# 06_GPRS.net
KiCad netlist of a schematic drawn in Altium Designer
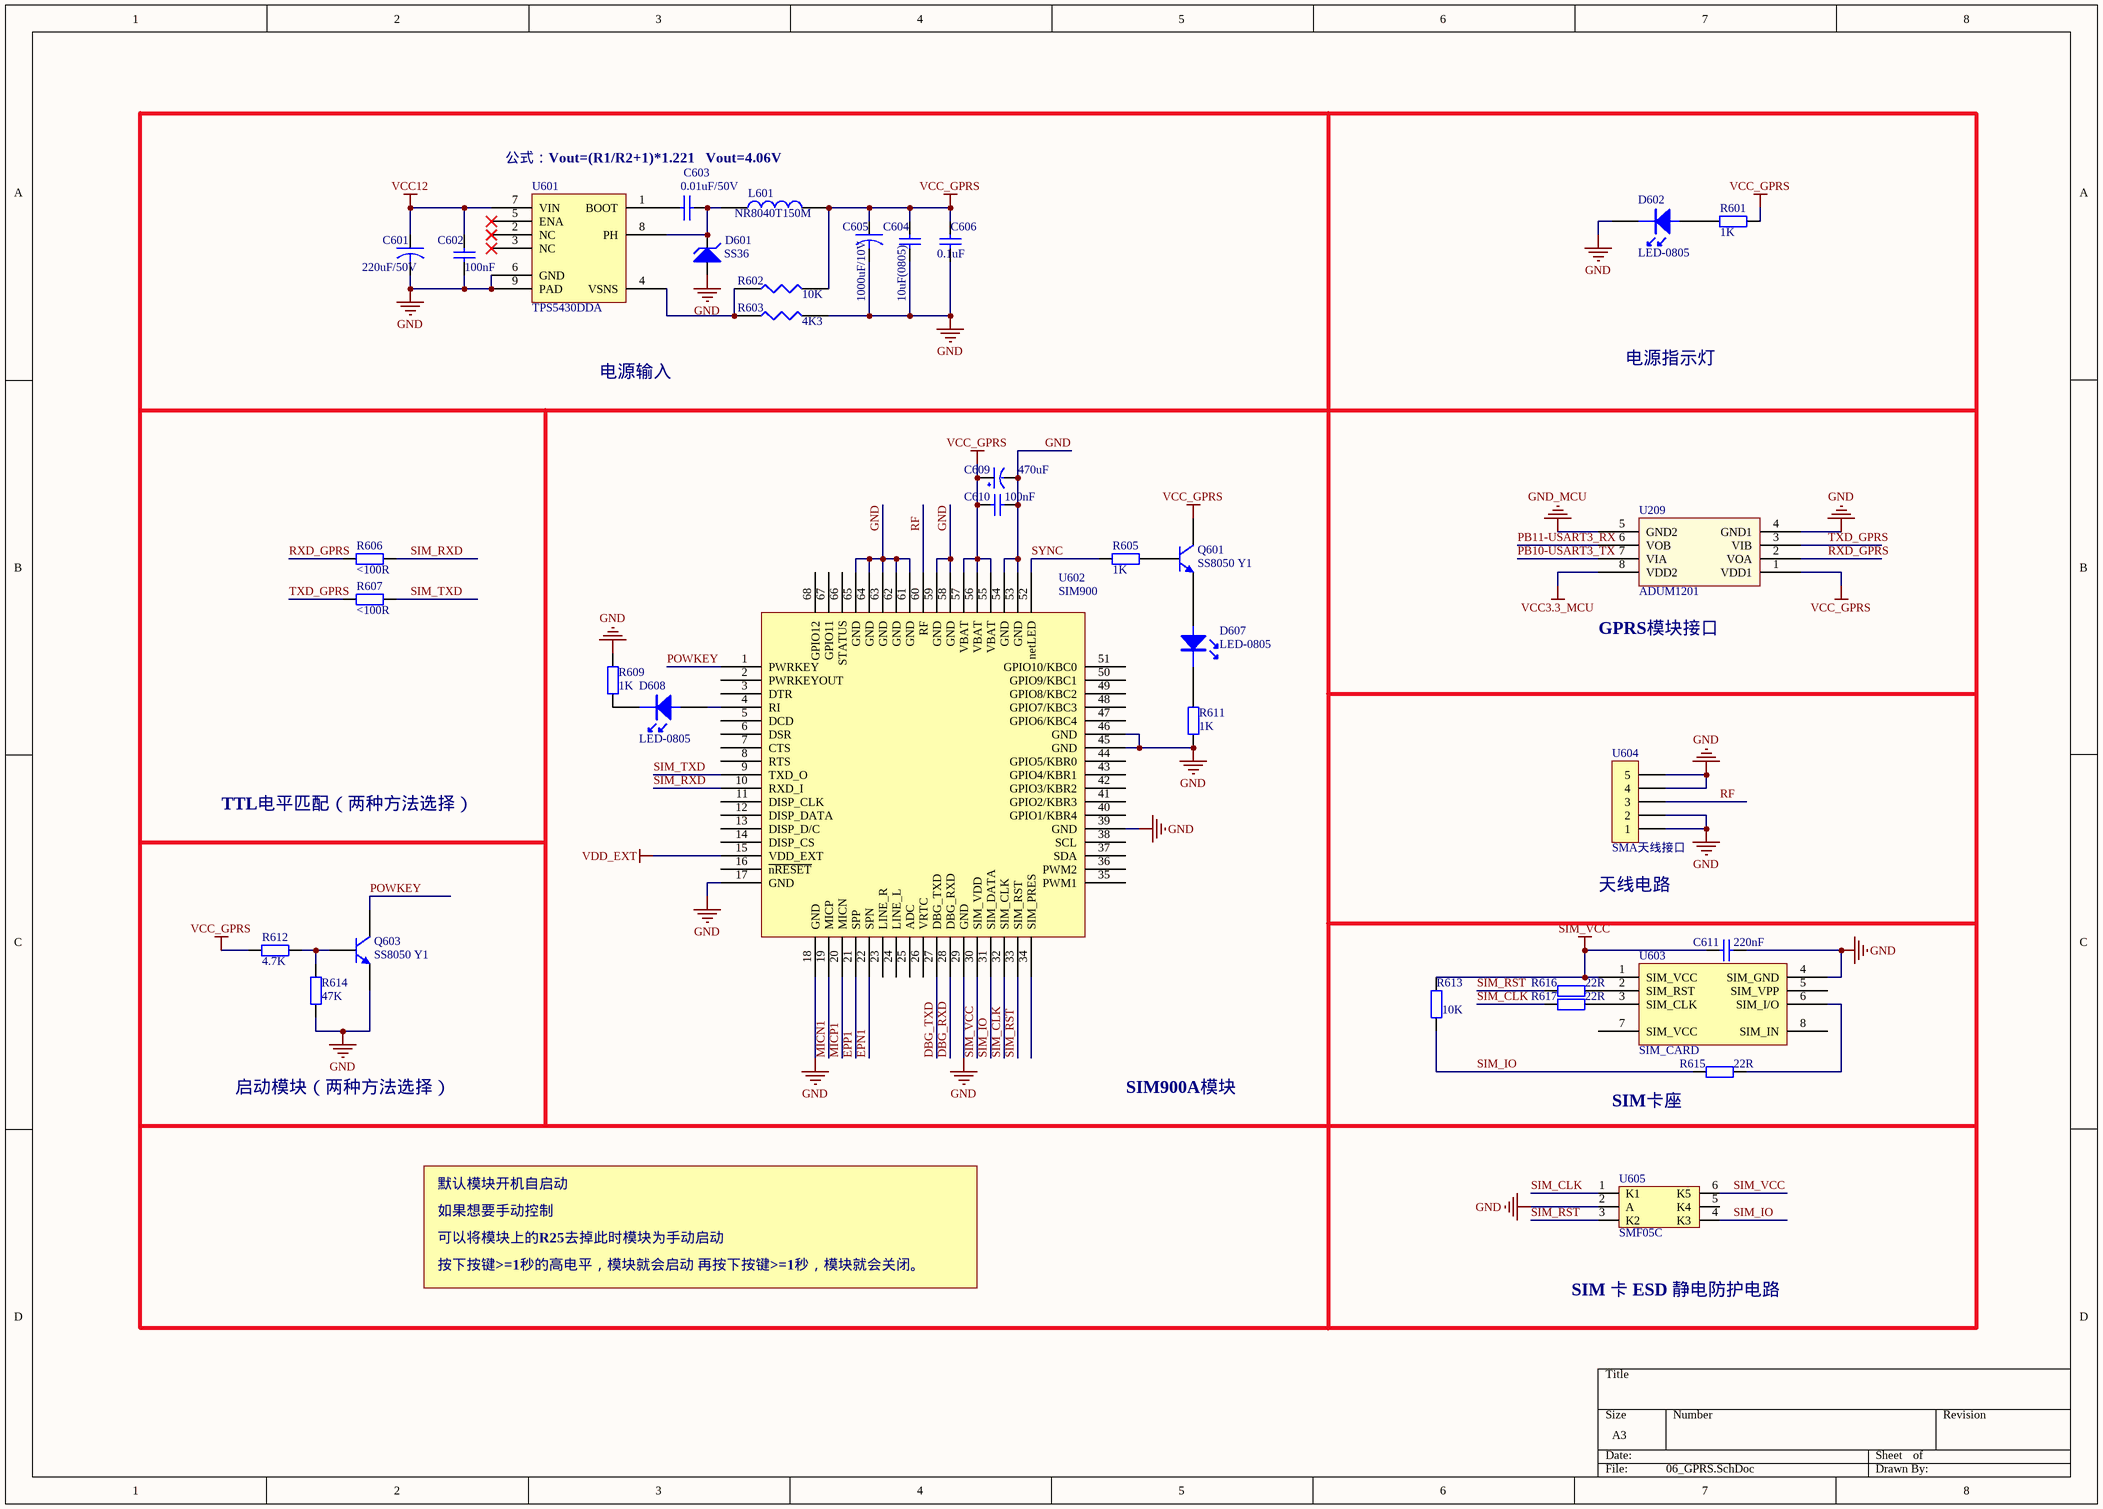
[diagram p0: 06_GPRS.SchDoc]

(export (version "E")
  (design (tool "Eeschema 10.0.6"))
  (components
    (comp (ref "C601")
      (value "220uF/50V")
      (footprint "CD's_LIB_2018:RB050-100")
      (description "Capacitor")
      (libsource (lib "*") (part "CAPACITOR"))
    )
    (comp (ref "C602")
      (value "100nF")
      (footprint "0805C")
      (description "贴片电容")
      (libsource (lib "Miscellaneous Devices LC") (part "0603 1uF (105) 10% 50V"))
    )
    (comp (ref "C603")
      (value "0.01uF/50V")
      (footprint "0603C")
      (description "Capacitor")
      (libsource (lib "*") (part "CAP"))
    )
    (comp (ref "C604")
      (value "10uF(0805)")
      (footprint "LC-0603_C")
      (description "贴片电容")
      (libsource (lib "Miscellaneous Devices LC") (part "0603 1uF (105) 10% 50V"))
    )
    (comp (ref "C605")
      (value "1000uF/10V")
      (footprint "RB035-080")
      (description "Capacitor")
      (libsource (lib "*") (part "CAPACITOR"))
    )
    (comp (ref "C606")
      (value "0.1uF")
      (footprint "LC-0603_C")
      (description "贴片电容")
      (libsource (lib "Miscellaneous Devices LC") (part "0603 1.0pF (010) 0.25pF 50V"))
    )
    (comp (ref "C609")
      (value "470uF")
      (footprint "CAP_10*10")
      (libsource (lib "Explorer STM32F407封装库") (part "CAP"))
    )
    (comp (ref "C610")
      (value "100nF")
      (footprint "LC-0603_C")
      (description "贴片电容")
      (libsource (lib "Miscellaneous Devices LC") (part "0603 1uF (105) 10% 50V"))
    )
    (comp (ref "C611")
      (value "220nF")
      (footprint "LC-0603_C")
      (description "贴片电容")
      (libsource (lib "Miscellaneous Devices LC") (part "0603 1uF (105) 10% 50V"))
    )
    (comp (ref "D601")
      (value "SS36")
      (footprint "D1812")
      (description "Zener Diode")
      (libsource (lib "*") (part "SS36"))
    )
    (comp (ref "D602")
      (value "LED-0805")
      (footprint "CD's_LIB_2018:0805LED")
      (description "贴片LED")
      (libsource (lib "CD's_LIB_2018") (part "LED_SMD"))
    )
    (comp (ref "D607")
      (value "LED-0805")
      (footprint "CD's_LIB_2018:0805LED")
      (description "贴片LED")
      (libsource (lib "CD's_LIB_2018") (part "LED_SMD"))
    )
    (comp (ref "D608")
      (value "LED-0805")
      (footprint "CD's_LIB_2018:0805LED")
      (description "贴片LED")
      (libsource (lib "CD's_LIB_2018") (part "LED_SMD"))
    )
    (comp (ref "L601") (value "NR8040T150M") (footprint "NR8040") (libsource (lib "*") (part "INDUCTOR")))
    (comp (ref "Q601")
      (value "SS8050 Y1")
      (footprint "LC-SOT-23(SOT-23-3)")
      (description "三极管")
      (libsource (lib "Miscellaneous Devices LC") (part "SOT-23 SS8050 Y1"))
    )
    (comp (ref "Q603")
      (value "SS8050 Y1")
      (footprint "LC-SOT-23(SOT-23-3)")
      (description "三极管")
      (libsource (lib "Miscellaneous Devices LC") (part "SOT-23 SS8050 Y1"))
    )
    (comp (ref "R601")
      (value "1K")
      (footprint "LC-0603_R")
      (description "贴片电阻")
      (libsource (lib "") (part "0603 2KΩ (2001) 1%_2"))
    )
    (comp (ref "R602") (value "10K") (footprint "0603R") (libsource (lib "*") (part "RES1")))
    (comp (ref "R603") (value "4K3") (footprint "0603R") (libsource (lib "*") (part "RES1")))
    (comp (ref "R605")
      (value "1K")
      (footprint "LC-0603_R")
      (description "贴片电阻")
      (libsource (lib "") (part "0603 2KΩ (2001) 1%_2"))
    )
    (comp (ref "R606")
      (value "<100R")
      (footprint "LC-0603_R")
      (description "贴片电阻")
      (libsource (lib "") (part "0603 2KΩ (2001) 1%_1"))
    )
    (comp (ref "R607")
      (value "<100R")
      (footprint "LC-0603_R")
      (description "贴片电阻")
      (libsource (lib "") (part "0603 2KΩ (2001) 1%_1"))
    )
    (comp (ref "R609")
      (value "1K")
      (footprint "LC-0603_R")
      (description "贴片电阻")
      (libsource (lib "") (part "0603 2KΩ (2001) 1%_3"))
    )
    (comp (ref "R611")
      (value "1K")
      (footprint "LC-0603_R")
      (description "贴片电阻")
      (libsource (lib "Miscellaneous Devices LC") (part "0603 2KΩ (2001) 1%"))
    )
    (comp (ref "R612")
      (value "4.7K")
      (footprint "LC-0603_R")
      (description "贴片电阻")
      (libsource (lib "") (part "0603 2KΩ (2001) 1%_1"))
    )
    (comp (ref "R613")
      (value "10K")
      (footprint "LC-0603_R")
      (description "贴片电阻")
      (libsource (lib "") (part "0603 2KΩ (2001) 1%_3"))
    )
    (comp (ref "R614")
      (value "47K")
      (footprint "LC-0603_R")
      (description "贴片电阻")
      (libsource (lib "") (part "0603 2KΩ (2001) 1%_3"))
    )
    (comp (ref "R615")
      (value "22R")
      (footprint "LC-0603_R")
      (description "贴片电阻")
      (libsource (lib "") (part "0603 2KΩ (2001) 1%_2"))
    )
    (comp (ref "R616")
      (value "22R")
      (footprint "LC-0603_R")
      (description "贴片电阻")
      (libsource (lib "") (part "0603 2KΩ (2001) 1%_2"))
    )
    (comp (ref "R617")
      (value "22R")
      (footprint "LC-0603_R")
      (description "贴片电阻")
      (libsource (lib "") (part "0603 2KΩ (2001) 1%_2"))
    )
    (comp (ref "U209")
      (value "ADUM1201")
      (footprint "SOP_8")
      (description "串口隔离")
      (libsource (lib "liu_2016") (part "ADUM1201"))
    )
    (comp (ref "U601") (value "TPS5430DDA") (footprint "SO-G8") (libsource (lib "*") (part "TPS5430DDA")))
    (comp (ref "U602")
      (value "SIM900")
      (footprint "SIM900A_mini:GSM_900A")
      (libsource (lib "ATK-SIM900A") (part "SIM900"))
    )
    (comp (ref "U603")
      (value "SIM_CARD")
      (footprint "MICRO SIM6")
      (description "SIM中卡卡槽")
      (libsource (lib "liu_2016") (part "SIM_CARD"))
    )
    (comp (ref "U604")
      (value "SMA天线接口")
      (footprint "RF_2")
      (description "Connector")
      (libsource (lib "CD's_LIB_2018") (part "CON5"))
    )
    (comp (ref "U605")
      (value "SMF05C")
      (footprint "SOT-363")
      (description "TVS")
      (libsource (lib "ATK-SIM900A GSM模块封装库") (part "SMF05C"))
    )
  )
  (nets
    (net (code "1") (name "/DBG_RXD") (class "Default")
      (node (ref "U602") (pin "28") (pinfunction "DBG_RXD_28") (pintype "passive"))
    )
    (net (code "2") (name "/DBG_TXD") (class "Default")
      (node (ref "U602") (pin "27") (pinfunction "DBG_TXD_27") (pintype "passive"))
    )
    (net (code "3") (name "/EPN1") (class "Default")
      (node (ref "U602") (pin "22") (pinfunction "SPN_22") (pintype "passive"))
    )
    (net (code "4") (name "/EPP1") (class "Default")
      (node (ref "U602") (pin "21") (pinfunction "SPP_21") (pintype "passive"))
    )
    (net (code "5") (name "/MICN1") (class "Default")
      (node (ref "U602") (pin "19") (pinfunction "MICP_19") (pintype "passive"))
    )
    (net (code "6") (name "/MICP1") (class "Default")
      (node (ref "U602") (pin "20") (pinfunction "MICN_20") (pintype "passive"))
    )
    (net (code "7") (name "/PB10-USART3_TX") (class "Default")
      (node (ref "U209") (pin "7") (pinfunction "VIA_7") (pintype "passive"))
    )
    (net (code "8") (name "/PB11-USART3_RX") (class "Default")
      (node (ref "U209") (pin "6") (pinfunction "VOB_6") (pintype "passive"))
    )
    (net (code "9") (name "/POWKEY") (class "Default")
      (node (ref "Q603") (pin "3") (pinfunction "C_3") (pintype "passive"))
      (node (ref "U602") (pin "1") (pinfunction "PWRKEY_1") (pintype "passive"))
    )
    (net (code "10") (name "/RF") (class "Default")
      (node (ref "U602") (pin "60") (pinfunction "RF_60") (pintype "passive"))
      (node (ref "U604") (pin "3") (pinfunction "3_3") (pintype "passive"))
    )
    (net (code "11") (name "/RXD_GPRS") (class "Default")
      (node (ref "R606") (pin "1") (pinfunction "1_1") (pintype "passive"))
      (node (ref "U209") (pin "2") (pinfunction "VOA_2") (pintype "passive"))
    )
    (net (code "12") (name "/SIM_CLK") (class "Default")
      (node (ref "R617") (pin "2") (pinfunction "2_2") (pintype "passive"))
      (node (ref "U602") (pin "32") (pinfunction "SIM_CLK_32") (pintype "passive"))
      (node (ref "U605") (pin "1") (pinfunction "K1_1") (pintype "passive"))
    )
    (net (code "13") (name "/SIM_IO") (class "Default")
      (node (ref "R613") (pin "1") (pinfunction "1_1") (pintype "passive"))
      (node (ref "R615") (pin "2") (pinfunction "2_2") (pintype "passive"))
      (node (ref "U602") (pin "31") (pinfunction "SIM_DATA_31") (pintype "passive"))
      (node (ref "U605") (pin "4") (pinfunction "K3_4") (pintype "passive"))
    )
    (net (code "14") (name "/SIM_RST") (class "Default")
      (node (ref "R616") (pin "2") (pinfunction "2_2") (pintype "passive"))
      (node (ref "U602") (pin "33") (pinfunction "SIM_RST_33") (pintype "passive"))
      (node (ref "U605") (pin "3") (pinfunction "K2_3") (pintype "passive"))
    )
    (net (code "15") (name "/SIM_RXD") (class "Default")
      (node (ref "R606") (pin "2") (pinfunction "2_2") (pintype "passive"))
      (node (ref "U602") (pin "10") (pinfunction "RXD_I_10") (pintype "passive"))
    )
    (net (code "16") (name "/SIM_TXD") (class "Default")
      (node (ref "R607") (pin "2") (pinfunction "2_2") (pintype "passive"))
      (node (ref "U602") (pin "9") (pinfunction "TXD_O_9") (pintype "passive"))
    )
    (net (code "17") (name "/SYNC") (class "Default")
      (node (ref "R605") (pin "2") (pinfunction "2_2") (pintype "passive"))
      (node (ref "U602") (pin "52") (pinfunction "netLED_52") (pintype "passive"))
    )
    (net (code "18") (name "/TXD_GPRS") (class "Default")
      (node (ref "R607") (pin "1") (pinfunction "1_1") (pintype "passive"))
      (node (ref "U209") (pin "3") (pinfunction "VIB_3") (pintype "passive"))
    )
    (net (code "19") (name "GND") (class "Default")
      (node (ref "C601") (pin "2") (pinfunction "2_2") (pintype "passive"))
      (node (ref "C602") (pin "2") (pinfunction "2_2") (pintype "passive"))
      (node (ref "C604") (pin "2") (pinfunction "2_2") (pintype "passive"))
      (node (ref "C605") (pin "2") (pinfunction "2_2") (pintype "passive"))
      (node (ref "C606") (pin "1") (pinfunction "1_1") (pintype "passive"))
      (node (ref "C609") (pin "2") (pinfunction "GND_2") (pintype "passive"))
      (node (ref "C610") (pin "2") (pinfunction "2_2") (pintype "passive"))
      (node (ref "C611") (pin "2") (pinfunction "2_2") (pintype "passive"))
      (node (ref "D601") (pin "1") (pinfunction "A_1") (pintype "passive"))
      (node (ref "D602") (pin "1") (pinfunction "-_1") (pintype "passive"))
      (node (ref "Q603") (pin "2") (pinfunction "E_2") (pintype "passive"))
      (node (ref "R603") (pin "2") (pinfunction "2_2") (pintype "passive"))
      (node (ref "R609") (pin "2") (pinfunction "2_2") (pintype "passive"))
      (node (ref "R611") (pin "2") (pinfunction "2_2") (pintype "passive"))
      (node (ref "R614") (pin "1") (pinfunction "1_1") (pintype "passive"))
      (node (ref "U209") (pin "4") (pinfunction "GND1_4") (pintype "passive"))
      (node (ref "U601") (pin "6") (pinfunction "GND_6") (pintype "passive"))
      (node (ref "U601") (pin "9") (pinfunction "PAD_9") (pintype "passive"))
      (node (ref "U602") (pin "17") (pinfunction "GND_17") (pintype "passive"))
      (node (ref "U602") (pin "18") (pinfunction "GND_18") (pintype "passive"))
      (node (ref "U602") (pin "29") (pinfunction "GND_29") (pintype "passive"))
      (node (ref "U602") (pin "39") (pinfunction "GND_39") (pintype "passive"))
      (node (ref "U602") (pin "45") (pinfunction "GND_45") (pintype "passive"))
      (node (ref "U602") (pin "46") (pinfunction "GND_46") (pintype "passive"))
      (node (ref "U602") (pin "53") (pinfunction "GND_53") (pintype "passive"))
      (node (ref "U602") (pin "54") (pinfunction "GND_54") (pintype "passive"))
      (node (ref "U602") (pin "58") (pinfunction "GND_58") (pintype "passive"))
      (node (ref "U602") (pin "59") (pinfunction "GND_59") (pintype "passive"))
      (node (ref "U602") (pin "61") (pinfunction "GND_61") (pintype "passive"))
      (node (ref "U602") (pin "62") (pinfunction "GND_62") (pintype "passive"))
      (node (ref "U602") (pin "63") (pinfunction "GND_63") (pintype "passive"))
      (node (ref "U602") (pin "64") (pinfunction "GND_64") (pintype "passive"))
      (node (ref "U602") (pin "65") (pinfunction "GND_65") (pintype "passive"))
      (node (ref "U603") (pin "4") (pinfunction "SIM_GND_4") (pintype "passive"))
      (node (ref "U604") (pin "1") (pinfunction "1_1") (pintype "passive"))
      (node (ref "U604") (pin "2") (pinfunction "2_2") (pintype "passive"))
      (node (ref "U604") (pin "4") (pinfunction "4_4") (pintype "passive"))
      (node (ref "U604") (pin "5") (pinfunction "5_5") (pintype "passive"))
      (node (ref "U605") (pin "2") (pinfunction "A_2") (pintype "passive"))
    )
    (net (code "20") (name "GND_MCU") (class "Default")
      (node (ref "U209") (pin "5") (pinfunction "GND2_5") (pintype "passive"))
    )
    (net (code "21") (name "Net-(D601-K)") (class "Default")
      (node (ref "C603") (pin "2") (pinfunction "2_2") (pintype "passive"))
      (node (ref "D601") (pin "2") (pinfunction "K_2") (pintype "passive"))
      (node (ref "L601") (pin "1") (pinfunction "1_1") (pintype "passive"))
      (node (ref "U601") (pin "8") (pinfunction "PH_8") (pintype "passive"))
    )
    (net (code "22") (name "Net-(D602-+)") (class "Default")
      (node (ref "D602") (pin "2") (pinfunction "+_2") (pintype "passive"))
      (node (ref "R601") (pin "2") (pinfunction "2_2") (pintype "passive"))
    )
    (net (code "23") (name "Net-(D607-+)") (class "Default")
      (node (ref "D607") (pin "2") (pinfunction "+_2") (pintype "passive"))
      (node (ref "Q601") (pin "2") (pinfunction "E_2") (pintype "passive"))
    )
    (net (code "24") (name "Net-(D607--)") (class "Default")
      (node (ref "D607") (pin "1") (pinfunction "-_1") (pintype "passive"))
      (node (ref "R611") (pin "1") (pinfunction "1_1") (pintype "passive"))
    )
    (net (code "25") (name "Net-(D608-+)") (class "Default")
      (node (ref "D608") (pin "2") (pinfunction "+_2") (pintype "passive"))
      (node (ref "U602") (pin "4") (pinfunction "RI_4") (pintype "passive"))
    )
    (net (code "26") (name "Net-(D608--)") (class "Default")
      (node (ref "D608") (pin "1") (pinfunction "-_1") (pintype "passive"))
      (node (ref "R609") (pin "1") (pinfunction "1_1") (pintype "passive"))
    )
    (net (code "27") (name "Net-(Q601-B)") (class "Default")
      (node (ref "Q601") (pin "1") (pinfunction "B_1") (pintype "passive"))
      (node (ref "R605") (pin "1") (pinfunction "1_1") (pintype "passive"))
    )
    (net (code "28") (name "Net-(Q603-B)") (class "Default")
      (node (ref "Q603") (pin "1") (pinfunction "B_1") (pintype "passive"))
      (node (ref "R612") (pin "2") (pinfunction "2_2") (pintype "passive"))
      (node (ref "R614") (pin "2") (pinfunction "2_2") (pintype "passive"))
    )
    (net (code "29") (name "Net-(U601-BOOT)") (class "Default")
      (node (ref "C603") (pin "1") (pinfunction "1_1") (pintype "passive"))
      (node (ref "U601") (pin "1") (pinfunction "BOOT_1") (pintype "passive"))
    )
    (net (code "30") (name "Net-(U601-VSNS)") (class "Default")
      (node (ref "R602") (pin "1") (pinfunction "1_1") (pintype "passive"))
      (node (ref "R603") (pin "1") (pinfunction "1_1") (pintype "passive"))
      (node (ref "U601") (pin "4") (pinfunction "VSNS_4") (pintype "passive"))
    )
    (net (code "31") (name "Net-(U603-SIM_CLK)") (class "Default")
      (node (ref "R617") (pin "1") (pinfunction "1_1") (pintype "passive"))
      (node (ref "U603") (pin "3") (pinfunction "SIM_CLK_3") (pintype "passive"))
    )
    (net (code "32") (name "Net-(U603-SIM_I{slash}O)") (class "Default")
      (node (ref "R615") (pin "1") (pinfunction "1_1") (pintype "passive"))
      (node (ref "U603") (pin "6") (pinfunction "SIM_I/O_6") (pintype "passive"))
    )
    (net (code "33") (name "Net-(U603-SIM_RST)") (class "Default")
      (node (ref "R616") (pin "1") (pinfunction "1_1") (pintype "passive"))
      (node (ref "U603") (pin "2") (pinfunction "SIM_RST_2") (pintype "passive"))
    )
    (net (code "34") (name "SIM_VCC") (class "Default")
      (node (ref "C611") (pin "1") (pinfunction "1_1") (pintype "passive"))
      (node (ref "R613") (pin "2") (pinfunction "2_2") (pintype "passive"))
      (node (ref "U602") (pin "30") (pinfunction "SIM_VDD_30") (pintype "passive"))
      (node (ref "U603") (pin "1") (pinfunction "SIM_VCC_1") (pintype "passive"))
      (node (ref "U605") (pin "6") (pinfunction "K5_6") (pintype "passive"))
    )
    (net (code "35") (name "VCC3.3_MCU") (class "Default")
      (node (ref "U209") (pin "8") (pinfunction "VDD2_8") (pintype "passive"))
    )
    (net (code "36") (name "VCC12") (class "Default")
      (node (ref "C601") (pin "1") (pinfunction "1_1") (pintype "passive"))
      (node (ref "C602") (pin "1") (pinfunction "1_1") (pintype "passive"))
      (node (ref "U601") (pin "7") (pinfunction "VIN_7") (pintype "passive"))
    )
    (net (code "37") (name "VCC_GPRS") (class "Default")
      (node (ref "C604") (pin "1") (pinfunction "1_1") (pintype "passive"))
      (node (ref "C605") (pin "1") (pinfunction "1_1") (pintype "passive"))
      (node (ref "C606") (pin "2") (pinfunction "2_2") (pintype "passive"))
      (node (ref "C609") (pin "1") (pinfunction "VCC_1") (pintype "passive"))
      (node (ref "C610") (pin "1") (pinfunction "1_1") (pintype "passive"))
      (node (ref "L601") (pin "2") (pinfunction "2_2") (pintype "passive"))
      (node (ref "Q601") (pin "3") (pinfunction "C_3") (pintype "passive"))
      (node (ref "R601") (pin "1") (pinfunction "1_1") (pintype "passive"))
      (node (ref "R602") (pin "2") (pinfunction "2_2") (pintype "passive"))
      (node (ref "R612") (pin "1") (pinfunction "1_1") (pintype "passive"))
      (node (ref "U209") (pin "1") (pinfunction "VDD1_1") (pintype "passive"))
      (node (ref "U602") (pin "55") (pinfunction "VBAT_55") (pintype "passive"))
      (node (ref "U602") (pin "56") (pinfunction "VBAT_56") (pintype "passive"))
      (node (ref "U602") (pin "57") (pinfunction "VBAT_57") (pintype "passive"))
    )
    (net (code "38") (name "VDD_EXT") (class "Default")
      (node (ref "U602") (pin "15") (pinfunction "VDD_EXT_15") (pintype "passive"))
    )
    (net (code "39") (name "unconnected-(U601-ENA-Pad5)") (class "Default")
      (node (ref "U601") (pin "5") (pinfunction "ENA_5") (pintype "passive+no_connect"))
    )
    (net (code "40") (name "unconnected-(U601-NC-Pad2)") (class "Default")
      (node (ref "U601") (pin "2") (pinfunction "NC_2") (pintype "passive+no_connect"))
    )
    (net (code "41") (name "unconnected-(U601-NC-Pad3)") (class "Default")
      (node (ref "U601") (pin "3") (pinfunction "NC_3") (pintype "passive+no_connect"))
    )
    (net (code "42") (name "unconnected-(U602-ADC-Pad25)") (class "Default")
      (node (ref "U602") (pin "25") (pinfunction "ADC_25") (pintype "passive"))
    )
    (net (code "43") (name "unconnected-(U602-CTS-Pad7)") (class "Default")
      (node (ref "U602") (pin "7") (pinfunction "CTS_7") (pintype "passive"))
    )
    (net (code "44") (name "unconnected-(U602-DCD-Pad5)") (class "Default")
      (node (ref "U602") (pin "5") (pinfunction "DCD_5") (pintype "passive"))
    )
    (net (code "45") (name "unconnected-(U602-DISP_CLK-Pad11)") (class "Default")
      (node (ref "U602") (pin "11") (pinfunction "DISP_CLK_11") (pintype "passive"))
    )
    (net (code "46") (name "unconnected-(U602-DISP_CS-Pad14)") (class "Default")
      (node (ref "U602") (pin "14") (pinfunction "DISP_CS_14") (pintype "passive"))
    )
    (net (code "47") (name "unconnected-(U602-DISP_DATA-Pad12)") (class "Default")
      (node (ref "U602") (pin "12") (pinfunction "DISP_DATA_12") (pintype "passive"))
    )
    (net (code "48") (name "unconnected-(U602-DISP_D{slash}C-Pad13)") (class "Default")
      (node (ref "U602") (pin "13") (pinfunction "DISP_D/C_13") (pintype "passive"))
    )
    (net (code "49") (name "unconnected-(U602-DSR-Pad6)") (class "Default")
      (node (ref "U602") (pin "6") (pinfunction "DSR_6") (pintype "passive"))
    )
    (net (code "50") (name "unconnected-(U602-DTR-Pad3)") (class "Default")
      (node (ref "U602") (pin "3") (pinfunction "DTR_3") (pintype "passive"))
    )
    (net (code "51") (name "unconnected-(U602-GPIO1{slash}KBR4-Pad40)") (class "Default")
      (node (ref "U602") (pin "40") (pinfunction "GPIO1/KBR4_40") (pintype "passive"))
    )
    (net (code "52") (name "unconnected-(U602-GPIO2{slash}KBR3-Pad41)") (class "Default")
      (node (ref "U602") (pin "41") (pinfunction "GPIO2/KBR3_41") (pintype "passive"))
    )
    (net (code "53") (name "unconnected-(U602-GPIO3{slash}KBR2-Pad42)") (class "Default")
      (node (ref "U602") (pin "42") (pinfunction "GPIO3/KBR2_42") (pintype "passive"))
    )
    (net (code "54") (name "unconnected-(U602-GPIO4{slash}KBR1-Pad43)") (class "Default")
      (node (ref "U602") (pin "43") (pinfunction "GPIO4/KBR1_43") (pintype "passive"))
    )
    (net (code "55") (name "unconnected-(U602-GPIO5{slash}KBR0-Pad44)") (class "Default")
      (node (ref "U602") (pin "44") (pinfunction "GPIO5/KBR0_44") (pintype "passive"))
    )
    (net (code "56") (name "unconnected-(U602-GPIO6{slash}KBC4-Pad47)") (class "Default")
      (node (ref "U602") (pin "47") (pinfunction "GPIO6/KBC4_47") (pintype "passive"))
    )
    (net (code "57") (name "unconnected-(U602-GPIO7{slash}KBC3-Pad48)") (class "Default")
      (node (ref "U602") (pin "48") (pinfunction "GPIO7/KBC3_48") (pintype "passive"))
    )
    (net (code "58") (name "unconnected-(U602-GPIO8{slash}KBC2-Pad49)") (class "Default")
      (node (ref "U602") (pin "49") (pinfunction "GPIO8/KBC2_49") (pintype "passive"))
    )
    (net (code "59") (name "unconnected-(U602-GPIO9{slash}KBC1-Pad50)") (class "Default")
      (node (ref "U602") (pin "50") (pinfunction "GPIO9/KBC1_50") (pintype "passive"))
    )
    (net (code "60") (name "unconnected-(U602-GPIO10{slash}KBC0-Pad51)") (class "Default")
      (node (ref "U602") (pin "51") (pinfunction "GPIO10/KBC0_51") (pintype "passive"))
    )
    (net (code "61") (name "unconnected-(U602-GPIO11-Pad67)") (class "Default")
      (node (ref "U602") (pin "67") (pinfunction "GPIO11_67") (pintype "passive"))
    )
    (net (code "62") (name "unconnected-(U602-GPIO12-Pad68)") (class "Default")
      (node (ref "U602") (pin "68") (pinfunction "GPIO12_68") (pintype "passive"))
    )
    (net (code "63") (name "unconnected-(U602-LINE_L-Pad24)") (class "Default")
      (node (ref "U602") (pin "24") (pinfunction "LINE_L_24") (pintype "passive"))
    )
    (net (code "64") (name "unconnected-(U602-LINE_R-Pad23)") (class "Default")
      (node (ref "U602") (pin "23") (pinfunction "LINE_R_23") (pintype "passive"))
    )
    (net (code "65") (name "unconnected-(U602-PWM1-Pad35)") (class "Default")
      (node (ref "U602") (pin "35") (pinfunction "PWM1_35") (pintype "passive"))
    )
    (net (code "66") (name "unconnected-(U602-PWM2-Pad36)") (class "Default")
      (node (ref "U602") (pin "36") (pinfunction "PWM2_36") (pintype "passive"))
    )
    (net (code "67") (name "unconnected-(U602-PWRKEYOUT-Pad2)") (class "Default")
      (node (ref "U602") (pin "2") (pinfunction "PWRKEYOUT_2") (pintype "passive"))
    )
    (net (code "68") (name "unconnected-(U602-RTS-Pad8)") (class "Default")
      (node (ref "U602") (pin "8") (pinfunction "RTS_8") (pintype "passive"))
    )
    (net (code "69") (name "unconnected-(U602-SCL-Pad38)") (class "Default")
      (node (ref "U602") (pin "38") (pinfunction "SCL_38") (pintype "passive"))
    )
    (net (code "70") (name "unconnected-(U602-SDA-Pad37)") (class "Default")
      (node (ref "U602") (pin "37") (pinfunction "SDA_37") (pintype "passive"))
    )
    (net (code "71") (name "unconnected-(U602-SIM_PRES-Pad34)") (class "Default")
      (node (ref "U602") (pin "34") (pinfunction "SIM_PRES_34") (pintype "passive"))
    )
    (net (code "72") (name "unconnected-(U602-STATUS-Pad66)") (class "Default")
      (node (ref "U602") (pin "66") (pinfunction "STATUS_66") (pintype "passive"))
    )
    (net (code "73") (name "unconnected-(U602-VRTC-Pad26)") (class "Default")
      (node (ref "U602") (pin "26") (pinfunction "VRTC_26") (pintype "passive"))
    )
    (net (code "74") (name "unconnected-(U602-~{nRESET}-Pad16)") (class "Default")
      (node (ref "U602") (pin "16") (pinfunction "~{nRESET}_16") (pintype "passive"))
    )
    (net (code "75") (name "unconnected-(U603-SIM_IN-Pad8)") (class "Default")
      (node (ref "U603") (pin "8") (pinfunction "SIM_IN_8") (pintype "passive"))
    )
    (net (code "76") (name "unconnected-(U603-SIM_VCC-Pad7)") (class "Default")
      (node (ref "U603") (pin "7") (pinfunction "SIM_VCC_7") (pintype "passive"))
    )
    (net (code "77") (name "unconnected-(U603-SIM_VPP-Pad5)") (class "Default")
      (node (ref "U603") (pin "5") (pinfunction "SIM_VPP_5") (pintype "passive"))
    )
    (net (code "78") (name "unconnected-(U605-K4-Pad5)") (class "Default")
      (node (ref "U605") (pin "5") (pinfunction "K4_5") (pintype "passive"))
    )
  )
)
